# do.net
KiCad netlist of a schematic drawn in Altium Designer
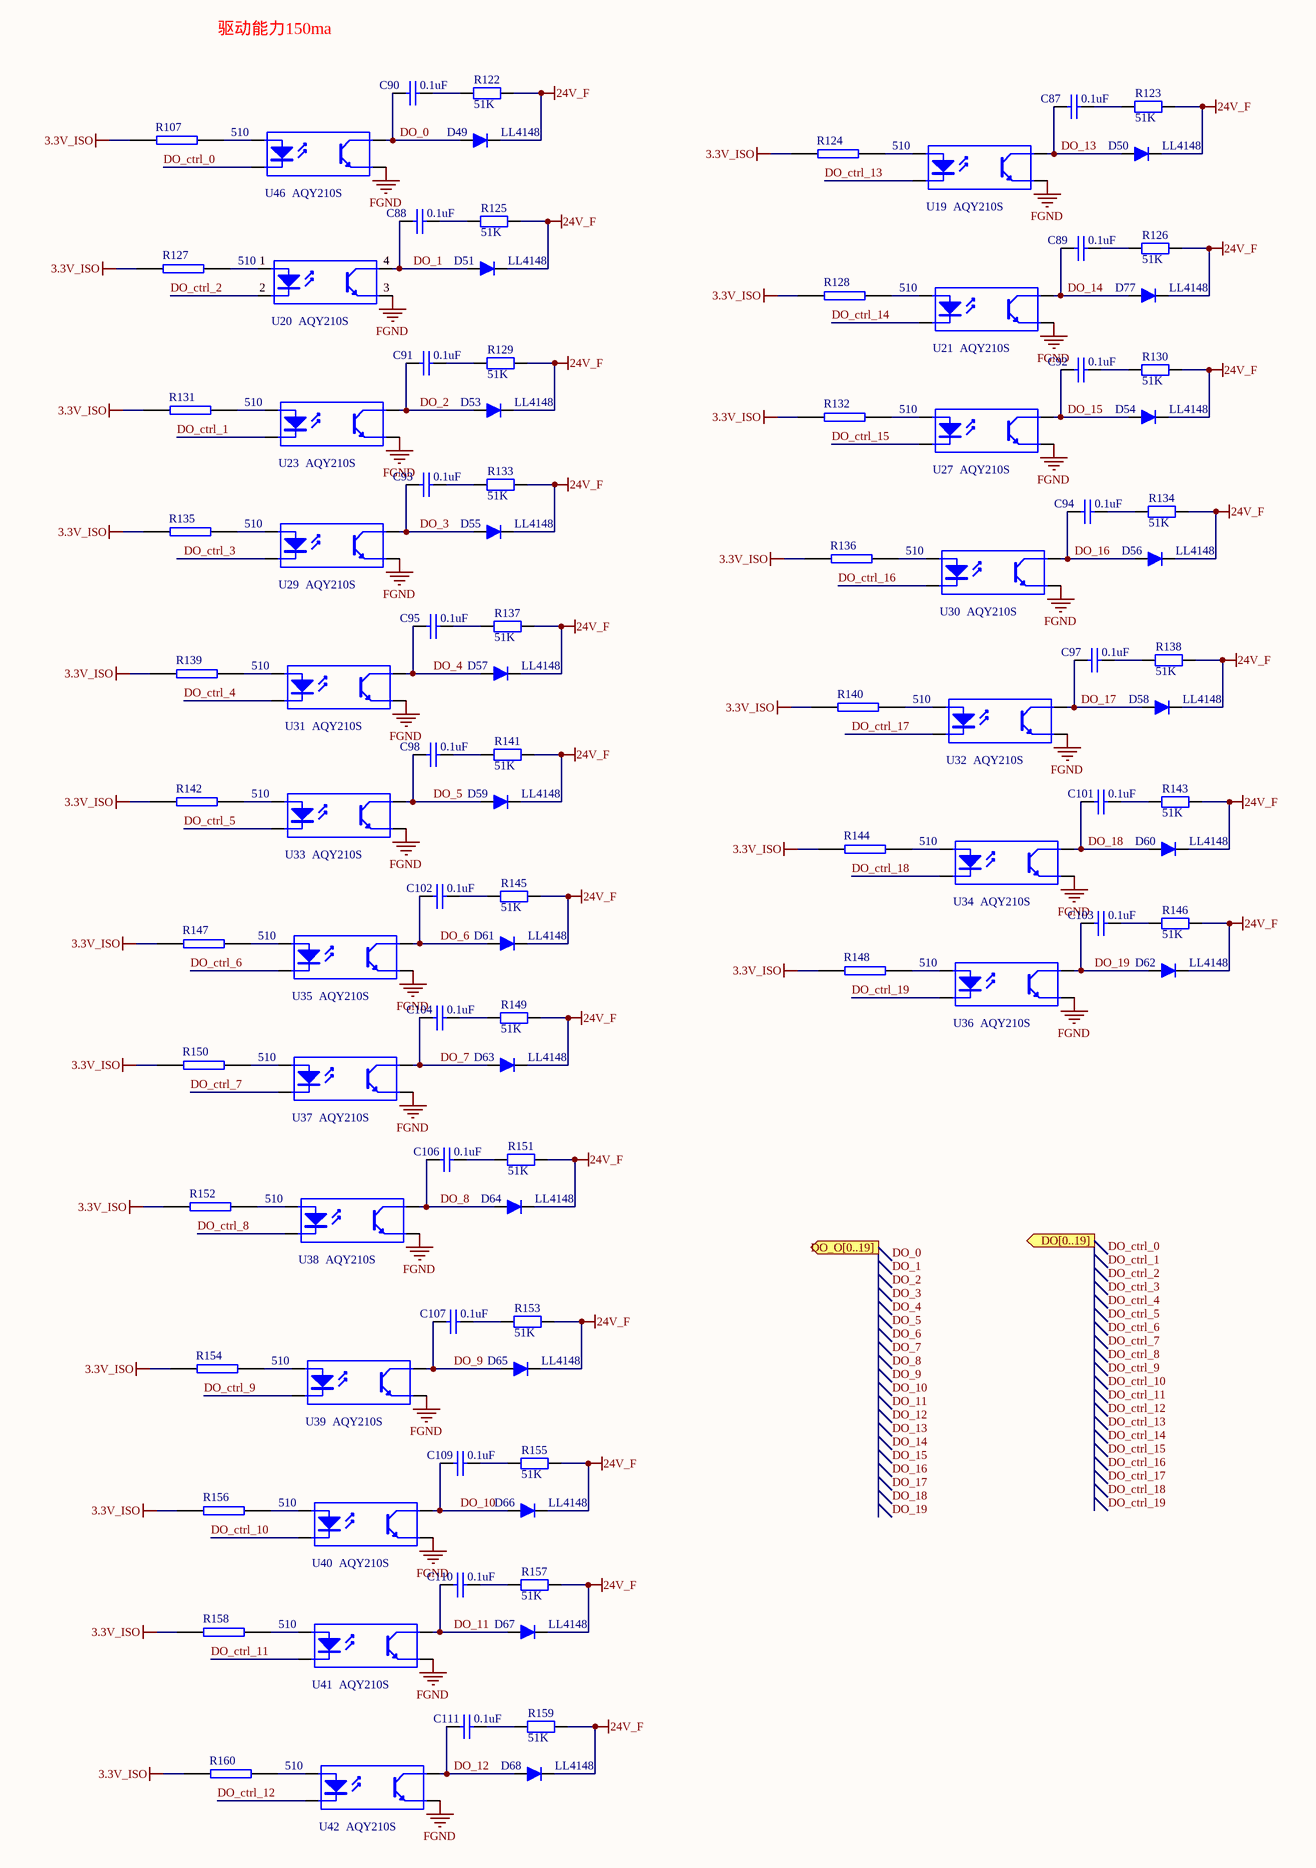
[diagram p0: do.SchDoc]

(export (version "E")
  (design (tool "Eeschema 10.0.6"))
  (components
    (comp (ref "C87")
      (value "0.1uF")
      (footprint "0603C")
      (description "Capacitor")
      (libsource (lib "*") (part "CAP"))
    )
    (comp (ref "C88")
      (value "0.1uF")
      (footprint "0603C")
      (description "Capacitor")
      (libsource (lib "*") (part "CAP"))
    )
    (comp (ref "C89")
      (value "0.1uF")
      (footprint "0603C")
      (description "Capacitor")
      (libsource (lib "*") (part "CAP"))
    )
    (comp (ref "C90")
      (value "0.1uF")
      (footprint "0603C")
      (description "Capacitor")
      (libsource (lib "*") (part "CAP"))
    )
    (comp (ref "C91")
      (value "0.1uF")
      (footprint "0603C")
      (description "Capacitor")
      (libsource (lib "*") (part "CAP"))
    )
    (comp (ref "C92")
      (value "0.1uF")
      (footprint "0603C")
      (description "Capacitor")
      (libsource (lib "*") (part "CAP"))
    )
    (comp (ref "C93")
      (value "0.1uF")
      (footprint "0603C")
      (description "Capacitor")
      (libsource (lib "*") (part "CAP"))
    )
    (comp (ref "C94")
      (value "0.1uF")
      (footprint "0603C")
      (description "Capacitor")
      (libsource (lib "*") (part "CAP"))
    )
    (comp (ref "C95")
      (value "0.1uF")
      (footprint "0603C")
      (description "Capacitor")
      (libsource (lib "*") (part "CAP"))
    )
    (comp (ref "C97")
      (value "0.1uF")
      (footprint "0603C")
      (description "Capacitor")
      (libsource (lib "*") (part "CAP"))
    )
    (comp (ref "C98")
      (value "0.1uF")
      (footprint "0603C")
      (description "Capacitor")
      (libsource (lib "*") (part "CAP"))
    )
    (comp (ref "C101")
      (value "0.1uF")
      (footprint "0603C")
      (description "Capacitor")
      (libsource (lib "*") (part "CAP"))
    )
    (comp (ref "C102")
      (value "0.1uF")
      (footprint "0603C")
      (description "Capacitor")
      (libsource (lib "*") (part "CAP"))
    )
    (comp (ref "C103")
      (value "0.1uF")
      (footprint "0603C")
      (description "Capacitor")
      (libsource (lib "*") (part "CAP"))
    )
    (comp (ref "C104")
      (value "0.1uF")
      (footprint "0603C")
      (description "Capacitor")
      (libsource (lib "*") (part "CAP"))
    )
    (comp (ref "C106")
      (value "0.1uF")
      (footprint "0603C")
      (description "Capacitor")
      (libsource (lib "*") (part "CAP"))
    )
    (comp (ref "C107")
      (value "0.1uF")
      (footprint "0603C")
      (description "Capacitor")
      (libsource (lib "*") (part "CAP"))
    )
    (comp (ref "C109")
      (value "0.1uF")
      (footprint "0603C")
      (description "Capacitor")
      (libsource (lib "*") (part "CAP"))
    )
    (comp (ref "C110")
      (value "0.1uF")
      (footprint "0603C")
      (description "Capacitor")
      (libsource (lib "*") (part "CAP"))
    )
    (comp (ref "C111")
      (value "0.1uF")
      (footprint "0603C")
      (description "Capacitor")
      (libsource (lib "*") (part "CAP"))
    )
    (comp (ref "D49")
      (value "LL4148")
      (footprint "DO-213AB/LL34/MiniMELF")
      (description "VISHAY,LL4148,圆柱体MiniMELF100V/2A,ROHS")
      (libsource (lib "Device2018") (part "LL4148"))
    )
    (comp (ref "D50")
      (value "LL4148")
      (footprint "DO-213AB/LL34/MiniMELF")
      (description "VISHAY,LL4148,圆柱体MiniMELF100V/2A,ROHS")
      (libsource (lib "Device2018") (part "LL4148"))
    )
    (comp (ref "D51")
      (value "LL4148")
      (footprint "DO-213AB/LL34/MiniMELF")
      (description "VISHAY,LL4148,圆柱体MiniMELF100V/2A,ROHS")
      (libsource (lib "Device2018") (part "LL4148"))
    )
    (comp (ref "D53")
      (value "LL4148")
      (footprint "DO-213AB/LL34/MiniMELF")
      (description "VISHAY,LL4148,圆柱体MiniMELF100V/2A,ROHS")
      (libsource (lib "Device2018") (part "LL4148"))
    )
    (comp (ref "D54")
      (value "LL4148")
      (footprint "DO-213AB/LL34/MiniMELF")
      (description "VISHAY,LL4148,圆柱体MiniMELF100V/2A,ROHS")
      (libsource (lib "Device2018") (part "LL4148"))
    )
    (comp (ref "D55")
      (value "LL4148")
      (footprint "DO-213AB/LL34/MiniMELF")
      (description "VISHAY,LL4148,圆柱体MiniMELF100V/2A,ROHS")
      (libsource (lib "Device2018") (part "LL4148"))
    )
    (comp (ref "D56")
      (value "LL4148")
      (footprint "DO-213AB/LL34/MiniMELF")
      (description "VISHAY,LL4148,圆柱体MiniMELF100V/2A,ROHS")
      (libsource (lib "Device2018") (part "LL4148"))
    )
    (comp (ref "D57")
      (value "LL4148")
      (footprint "DO-213AB/LL34/MiniMELF")
      (description "VISHAY,LL4148,圆柱体MiniMELF100V/2A,ROHS")
      (libsource (lib "Device2018") (part "LL4148"))
    )
    (comp (ref "D58")
      (value "LL4148")
      (footprint "DO-213AB/LL34/MiniMELF")
      (description "VISHAY,LL4148,圆柱体MiniMELF100V/2A,ROHS")
      (libsource (lib "Device2018") (part "LL4148"))
    )
    (comp (ref "D59")
      (value "LL4148")
      (footprint "DO-213AB/LL34/MiniMELF")
      (description "VISHAY,LL4148,圆柱体MiniMELF100V/2A,ROHS")
      (libsource (lib "Device2018") (part "LL4148"))
    )
    (comp (ref "D60")
      (value "LL4148")
      (footprint "DO-213AB/LL34/MiniMELF")
      (description "VISHAY,LL4148,圆柱体MiniMELF100V/2A,ROHS")
      (libsource (lib "Device2018") (part "LL4148"))
    )
    (comp (ref "D61")
      (value "LL4148")
      (footprint "DO-213AB/LL34/MiniMELF")
      (description "VISHAY,LL4148,圆柱体MiniMELF100V/2A,ROHS")
      (libsource (lib "Device2018") (part "LL4148"))
    )
    (comp (ref "D62")
      (value "LL4148")
      (footprint "DO-213AB/LL34/MiniMELF")
      (description "VISHAY,LL4148,圆柱体MiniMELF100V/2A,ROHS")
      (libsource (lib "Device2018") (part "LL4148"))
    )
    (comp (ref "D63")
      (value "LL4148")
      (footprint "DO-213AB/LL34/MiniMELF")
      (description "VISHAY,LL4148,圆柱体MiniMELF100V/2A,ROHS")
      (libsource (lib "Device2018") (part "LL4148"))
    )
    (comp (ref "D64")
      (value "LL4148")
      (footprint "DO-213AB/LL34/MiniMELF")
      (description "VISHAY,LL4148,圆柱体MiniMELF100V/2A,ROHS")
      (libsource (lib "Device2018") (part "LL4148"))
    )
    (comp (ref "D65")
      (value "LL4148")
      (footprint "DO-213AB/LL34/MiniMELF")
      (description "VISHAY,LL4148,圆柱体MiniMELF100V/2A,ROHS")
      (libsource (lib "Device2018") (part "LL4148"))
    )
    (comp (ref "D66")
      (value "LL4148")
      (footprint "DO-213AB/LL34/MiniMELF")
      (description "VISHAY,LL4148,圆柱体MiniMELF100V/2A,ROHS")
      (libsource (lib "Device2018") (part "LL4148"))
    )
    (comp (ref "D67")
      (value "LL4148")
      (footprint "DO-213AB/LL34/MiniMELF")
      (description "VISHAY,LL4148,圆柱体MiniMELF100V/2A,ROHS")
      (libsource (lib "Device2018") (part "LL4148"))
    )
    (comp (ref "D68")
      (value "LL4148")
      (footprint "DO-213AB/LL34/MiniMELF")
      (description "VISHAY,LL4148,圆柱体MiniMELF100V/2A,ROHS")
      (libsource (lib "Device2018") (part "LL4148"))
    )
    (comp (ref "D77")
      (value "LL4148")
      (footprint "DO-213AB/LL34/MiniMELF")
      (description "VISHAY,LL4148,圆柱体MiniMELF100V/2A,ROHS")
      (libsource (lib "Device2018") (part "LL4148"))
    )
    (comp (ref "R107") (value "510") (footprint "0603R") (libsource (lib "*") (part "RES2")))
    (comp (ref "R122") (value "51K") (footprint "0603R") (libsource (lib "MQlibrary") (part "Res0805M")))
    (comp (ref "R123") (value "51K") (footprint "0603R") (libsource (lib "MQlibrary") (part "Res0805M")))
    (comp (ref "R124") (value "510") (footprint "0603R") (libsource (lib "*") (part "RES2")))
    (comp (ref "R125") (value "51K") (footprint "0603R") (libsource (lib "MQlibrary") (part "Res0805M")))
    (comp (ref "R126") (value "51K") (footprint "0603R") (libsource (lib "MQlibrary") (part "Res0805M")))
    (comp (ref "R127") (value "510") (footprint "0603R") (libsource (lib "*") (part "RES2")))
    (comp (ref "R128") (value "510") (footprint "0603R") (libsource (lib "*") (part "RES2")))
    (comp (ref "R129") (value "51K") (footprint "0603R") (libsource (lib "MQlibrary") (part "Res0805M")))
    (comp (ref "R130") (value "51K") (footprint "0603R") (libsource (lib "MQlibrary") (part "Res0805M")))
    (comp (ref "R131") (value "510") (footprint "0603R") (libsource (lib "*") (part "RES2")))
    (comp (ref "R132") (value "510") (footprint "0603R") (libsource (lib "*") (part "RES2")))
    (comp (ref "R133") (value "51K") (footprint "0603R") (libsource (lib "MQlibrary") (part "Res0805M")))
    (comp (ref "R134") (value "51K") (footprint "0603R") (libsource (lib "MQlibrary") (part "Res0805M")))
    (comp (ref "R135") (value "510") (footprint "0603R") (libsource (lib "*") (part "RES2")))
    (comp (ref "R136") (value "510") (footprint "0603R") (libsource (lib "*") (part "RES2")))
    (comp (ref "R137") (value "51K") (footprint "0603R") (libsource (lib "MQlibrary") (part "Res0805M")))
    (comp (ref "R138") (value "51K") (footprint "0603R") (libsource (lib "MQlibrary") (part "Res0805M")))
    (comp (ref "R139") (value "510") (footprint "0603R") (libsource (lib "*") (part "RES2")))
    (comp (ref "R140") (value "510") (footprint "0603R") (libsource (lib "*") (part "RES2")))
    (comp (ref "R141") (value "51K") (footprint "0603R") (libsource (lib "MQlibrary") (part "Res0805M")))
    (comp (ref "R142") (value "510") (footprint "0603R") (libsource (lib "*") (part "RES2")))
    (comp (ref "R143") (value "51K") (footprint "0603R") (libsource (lib "MQlibrary") (part "Res0805M")))
    (comp (ref "R144") (value "510") (footprint "0603R") (libsource (lib "*") (part "RES2")))
    (comp (ref "R145") (value "51K") (footprint "0603R") (libsource (lib "MQlibrary") (part "Res0805M")))
    (comp (ref "R146") (value "51K") (footprint "0603R") (libsource (lib "MQlibrary") (part "Res0805M")))
    (comp (ref "R147") (value "510") (footprint "0603R") (libsource (lib "*") (part "RES2")))
    (comp (ref "R148") (value "510") (footprint "0603R") (libsource (lib "*") (part "RES2")))
    (comp (ref "R149") (value "51K") (footprint "0603R") (libsource (lib "MQlibrary") (part "Res0805M")))
    (comp (ref "R150") (value "510") (footprint "0603R") (libsource (lib "*") (part "RES2")))
    (comp (ref "R151") (value "51K") (footprint "0603R") (libsource (lib "MQlibrary") (part "Res0805M")))
    (comp (ref "R152") (value "510") (footprint "0603R") (libsource (lib "*") (part "RES2")))
    (comp (ref "R153") (value "51K") (footprint "0603R") (libsource (lib "MQlibrary") (part "Res0805M")))
    (comp (ref "R154") (value "510") (footprint "0603R") (libsource (lib "*") (part "RES2")))
    (comp (ref "R155") (value "51K") (footprint "0603R") (libsource (lib "MQlibrary") (part "Res0805M")))
    (comp (ref "R156") (value "510") (footprint "0603R") (libsource (lib "*") (part "RES2")))
    (comp (ref "R157") (value "51K") (footprint "0603R") (libsource (lib "MQlibrary") (part "Res0805M")))
    (comp (ref "R158") (value "510") (footprint "0603R") (libsource (lib "*") (part "RES2")))
    (comp (ref "R159") (value "51K") (footprint "0603R") (libsource (lib "MQlibrary") (part "Res0805M")))
    (comp (ref "R160") (value "510") (footprint "0603R") (libsource (lib "*") (part "RES2")))
    (comp (ref "U19")
      (value "AQY210S")
      (footprint "sop4")
      (description "4-Pin Phototransistor Optocoupler")
      (fields (field (name "PUBLISHER") "Altium Limited"))
      (libsource (lib "Miscellaneous Devices") (part "Optoisolator1"))
    )
    (comp (ref "U20")
      (value "AQY210S")
      (footprint "sop4")
      (description "4-Pin Phototransistor Optocoupler")
      (fields (field (name "PUBLISHER") "Altium Limited"))
      (libsource (lib "") (part "Optoisolator1_1"))
    )
    (comp (ref "U21")
      (value "AQY210S")
      (footprint "sop4")
      (description "4-Pin Phototransistor Optocoupler")
      (fields (field (name "PUBLISHER") "Altium Limited"))
      (libsource (lib "Miscellaneous Devices") (part "Optoisolator1"))
    )
    (comp (ref "U23")
      (value "AQY210S")
      (footprint "sop4")
      (description "4-Pin Phototransistor Optocoupler")
      (fields (field (name "PUBLISHER") "Altium Limited"))
      (libsource (lib "Miscellaneous Devices") (part "Optoisolator1"))
    )
    (comp (ref "U27")
      (value "AQY210S")
      (footprint "sop4")
      (description "4-Pin Phototransistor Optocoupler")
      (fields (field (name "PUBLISHER") "Altium Limited"))
      (libsource (lib "Miscellaneous Devices") (part "Optoisolator1"))
    )
    (comp (ref "U29")
      (value "AQY210S")
      (footprint "sop4")
      (description "4-Pin Phototransistor Optocoupler")
      (fields (field (name "PUBLISHER") "Altium Limited"))
      (libsource (lib "Miscellaneous Devices") (part "Optoisolator1"))
    )
    (comp (ref "U30")
      (value "AQY210S")
      (footprint "sop4")
      (description "4-Pin Phototransistor Optocoupler")
      (fields (field (name "PUBLISHER") "Altium Limited"))
      (libsource (lib "Miscellaneous Devices") (part "Optoisolator1"))
    )
    (comp (ref "U31")
      (value "AQY210S")
      (footprint "sop4")
      (description "4-Pin Phototransistor Optocoupler")
      (fields (field (name "PUBLISHER") "Altium Limited"))
      (libsource (lib "Miscellaneous Devices") (part "Optoisolator1"))
    )
    (comp (ref "U32")
      (value "AQY210S")
      (footprint "sop4")
      (description "4-Pin Phototransistor Optocoupler")
      (fields (field (name "PUBLISHER") "Altium Limited"))
      (libsource (lib "Miscellaneous Devices") (part "Optoisolator1"))
    )
    (comp (ref "U33")
      (value "AQY210S")
      (footprint "sop4")
      (description "4-Pin Phototransistor Optocoupler")
      (fields (field (name "PUBLISHER") "Altium Limited"))
      (libsource (lib "Miscellaneous Devices") (part "Optoisolator1"))
    )
    (comp (ref "U34")
      (value "AQY210S")
      (footprint "sop4")
      (description "4-Pin Phototransistor Optocoupler")
      (fields (field (name "PUBLISHER") "Altium Limited"))
      (libsource (lib "Miscellaneous Devices") (part "Optoisolator1"))
    )
    (comp (ref "U35")
      (value "AQY210S")
      (footprint "sop4")
      (description "4-Pin Phototransistor Optocoupler")
      (fields (field (name "PUBLISHER") "Altium Limited"))
      (libsource (lib "Miscellaneous Devices") (part "Optoisolator1"))
    )
    (comp (ref "U36")
      (value "AQY210S")
      (footprint "sop4")
      (description "4-Pin Phototransistor Optocoupler")
      (fields (field (name "PUBLISHER") "Altium Limited"))
      (libsource (lib "Miscellaneous Devices") (part "Optoisolator1"))
    )
    (comp (ref "U37")
      (value "AQY210S")
      (footprint "sop4")
      (description "4-Pin Phototransistor Optocoupler")
      (fields (field (name "PUBLISHER") "Altium Limited"))
      (libsource (lib "Miscellaneous Devices") (part "Optoisolator1"))
    )
    (comp (ref "U38")
      (value "AQY210S")
      (footprint "sop4")
      (description "4-Pin Phototransistor Optocoupler")
      (fields (field (name "PUBLISHER") "Altium Limited"))
      (libsource (lib "Miscellaneous Devices") (part "Optoisolator1"))
    )
    (comp (ref "U39")
      (value "AQY210S")
      (footprint "sop4")
      (description "4-Pin Phototransistor Optocoupler")
      (fields (field (name "PUBLISHER") "Altium Limited"))
      (libsource (lib "Miscellaneous Devices") (part "Optoisolator1"))
    )
    (comp (ref "U40")
      (value "AQY210S")
      (footprint "sop4")
      (description "4-Pin Phototransistor Optocoupler")
      (fields (field (name "PUBLISHER") "Altium Limited"))
      (libsource (lib "Miscellaneous Devices") (part "Optoisolator1"))
    )
    (comp (ref "U41")
      (value "AQY210S")
      (footprint "sop4")
      (description "4-Pin Phototransistor Optocoupler")
      (fields (field (name "PUBLISHER") "Altium Limited"))
      (libsource (lib "Miscellaneous Devices") (part "Optoisolator1"))
    )
    (comp (ref "U42")
      (value "AQY210S")
      (footprint "sop4")
      (description "4-Pin Phototransistor Optocoupler")
      (fields (field (name "PUBLISHER") "Altium Limited"))
      (libsource (lib "Miscellaneous Devices") (part "Optoisolator1"))
    )
    (comp (ref "U46")
      (value "AQY210S")
      (footprint "sop4")
      (description "4-Pin Phototransistor Optocoupler")
      (fields (field (name "PUBLISHER") "Altium Limited"))
      (libsource (lib "Miscellaneous Devices") (part "Optoisolator1"))
    )
  )
  (nets
    (net (code "42") (name "/DO_0") (class "Default")
      (node (ref "C90") (pin "1") (pinfunction "1_1") (pintype "passive"))
      (node (ref "D49") (pin "2") (pinfunction "2_2") (pintype "passive"))
      (node (ref "U46") (pin "4") (pinfunction "C_4") (pintype "passive"))
    )
    (net (code "43") (name "/DO_1") (class "Default")
      (node (ref "C88") (pin "1") (pinfunction "1_1") (pintype "passive"))
      (node (ref "D51") (pin "2") (pinfunction "2_2") (pintype "passive"))
      (node (ref "U20") (pin "4") (pinfunction "C_4") (pintype "passive"))
    )
    (net (code "44") (name "/DO_2") (class "Default")
      (node (ref "C91") (pin "1") (pinfunction "1_1") (pintype "passive"))
      (node (ref "D53") (pin "2") (pinfunction "2_2") (pintype "passive"))
      (node (ref "U23") (pin "4") (pinfunction "C_4") (pintype "passive"))
    )
    (net (code "45") (name "/DO_3") (class "Default")
      (node (ref "C93") (pin "1") (pinfunction "1_1") (pintype "passive"))
      (node (ref "D55") (pin "2") (pinfunction "2_2") (pintype "passive"))
      (node (ref "U29") (pin "4") (pinfunction "C_4") (pintype "passive"))
    )
    (net (code "46") (name "/DO_4") (class "Default")
      (node (ref "C95") (pin "1") (pinfunction "1_1") (pintype "passive"))
      (node (ref "D57") (pin "2") (pinfunction "2_2") (pintype "passive"))
      (node (ref "U31") (pin "4") (pinfunction "C_4") (pintype "passive"))
    )
    (net (code "47") (name "/DO_5") (class "Default")
      (node (ref "C98") (pin "1") (pinfunction "1_1") (pintype "passive"))
      (node (ref "D59") (pin "2") (pinfunction "2_2") (pintype "passive"))
      (node (ref "U33") (pin "4") (pinfunction "C_4") (pintype "passive"))
    )
    (net (code "48") (name "/DO_6") (class "Default")
      (node (ref "C102") (pin "1") (pinfunction "1_1") (pintype "passive"))
      (node (ref "D61") (pin "2") (pinfunction "2_2") (pintype "passive"))
      (node (ref "U35") (pin "4") (pinfunction "C_4") (pintype "passive"))
    )
    (net (code "49") (name "/DO_7") (class "Default")
      (node (ref "C104") (pin "1") (pinfunction "1_1") (pintype "passive"))
      (node (ref "D63") (pin "2") (pinfunction "2_2") (pintype "passive"))
      (node (ref "U37") (pin "4") (pinfunction "C_4") (pintype "passive"))
    )
    (net (code "50") (name "/DO_8") (class "Default")
      (node (ref "C106") (pin "1") (pinfunction "1_1") (pintype "passive"))
      (node (ref "D64") (pin "2") (pinfunction "2_2") (pintype "passive"))
      (node (ref "U38") (pin "4") (pinfunction "C_4") (pintype "passive"))
    )
    (net (code "51") (name "/DO_9") (class "Default")
      (node (ref "C107") (pin "1") (pinfunction "1_1") (pintype "passive"))
      (node (ref "D65") (pin "2") (pinfunction "2_2") (pintype "passive"))
      (node (ref "U39") (pin "4") (pinfunction "C_4") (pintype "passive"))
    )
    (net (code "52") (name "/DO_10") (class "Default")
      (node (ref "C109") (pin "1") (pinfunction "1_1") (pintype "passive"))
      (node (ref "D66") (pin "2") (pinfunction "2_2") (pintype "passive"))
      (node (ref "U40") (pin "4") (pinfunction "C_4") (pintype "passive"))
    )
    (net (code "53") (name "/DO_11") (class "Default")
      (node (ref "C110") (pin "1") (pinfunction "1_1") (pintype "passive"))
      (node (ref "D67") (pin "2") (pinfunction "2_2") (pintype "passive"))
      (node (ref "U41") (pin "4") (pinfunction "C_4") (pintype "passive"))
    )
    (net (code "54") (name "/DO_12") (class "Default")
      (node (ref "C111") (pin "1") (pinfunction "1_1") (pintype "passive"))
      (node (ref "D68") (pin "2") (pinfunction "2_2") (pintype "passive"))
      (node (ref "U42") (pin "4") (pinfunction "C_4") (pintype "passive"))
    )
    (net (code "55") (name "/DO_13") (class "Default")
      (node (ref "C87") (pin "1") (pinfunction "1_1") (pintype "passive"))
      (node (ref "D50") (pin "2") (pinfunction "2_2") (pintype "passive"))
      (node (ref "U19") (pin "4") (pinfunction "C_4") (pintype "passive"))
    )
    (net (code "56") (name "/DO_14") (class "Default")
      (node (ref "C89") (pin "1") (pinfunction "1_1") (pintype "passive"))
      (node (ref "D77") (pin "2") (pinfunction "2_2") (pintype "passive"))
      (node (ref "U21") (pin "4") (pinfunction "C_4") (pintype "passive"))
    )
    (net (code "57") (name "/DO_15") (class "Default")
      (node (ref "C92") (pin "1") (pinfunction "1_1") (pintype "passive"))
      (node (ref "D54") (pin "2") (pinfunction "2_2") (pintype "passive"))
      (node (ref "U27") (pin "4") (pinfunction "C_4") (pintype "passive"))
    )
    (net (code "58") (name "/DO_16") (class "Default")
      (node (ref "C94") (pin "1") (pinfunction "1_1") (pintype "passive"))
      (node (ref "D56") (pin "2") (pinfunction "2_2") (pintype "passive"))
      (node (ref "U30") (pin "4") (pinfunction "C_4") (pintype "passive"))
    )
    (net (code "59") (name "/DO_17") (class "Default")
      (node (ref "C97") (pin "1") (pinfunction "1_1") (pintype "passive"))
      (node (ref "D58") (pin "2") (pinfunction "2_2") (pintype "passive"))
      (node (ref "U32") (pin "4") (pinfunction "C_4") (pintype "passive"))
    )
    (net (code "60") (name "/DO_18") (class "Default")
      (node (ref "C101") (pin "1") (pinfunction "1_1") (pintype "passive"))
      (node (ref "D60") (pin "2") (pinfunction "2_2") (pintype "passive"))
      (node (ref "U34") (pin "4") (pinfunction "C_4") (pintype "passive"))
    )
    (net (code "61") (name "/DO_19") (class "Default")
      (node (ref "C103") (pin "1") (pinfunction "1_1") (pintype "passive"))
      (node (ref "D62") (pin "2") (pinfunction "2_2") (pintype "passive"))
      (node (ref "U36") (pin "4") (pinfunction "C_4") (pintype "passive"))
    )
    (net (code "63") (name "/DO_ctrl_0") (class "Default")
      (node (ref "U46") (pin "2") (pinfunction "K_2") (pintype "passive"))
    )
    (net (code "64") (name "/DO_ctrl_1") (class "Default")
      (node (ref "U23") (pin "2") (pinfunction "K_2") (pintype "passive"))
    )
    (net (code "65") (name "/DO_ctrl_2") (class "Default")
      (node (ref "U20") (pin "2") (pinfunction "K_2") (pintype "passive"))
    )
    (net (code "66") (name "/DO_ctrl_3") (class "Default")
      (node (ref "U29") (pin "2") (pinfunction "K_2") (pintype "passive"))
    )
    (net (code "67") (name "/DO_ctrl_4") (class "Default")
      (node (ref "U31") (pin "2") (pinfunction "K_2") (pintype "passive"))
    )
    (net (code "68") (name "/DO_ctrl_5") (class "Default")
      (node (ref "U33") (pin "2") (pinfunction "K_2") (pintype "passive"))
    )
    (net (code "69") (name "/DO_ctrl_6") (class "Default")
      (node (ref "U35") (pin "2") (pinfunction "K_2") (pintype "passive"))
    )
    (net (code "70") (name "/DO_ctrl_7") (class "Default")
      (node (ref "U37") (pin "2") (pinfunction "K_2") (pintype "passive"))
    )
    (net (code "71") (name "/DO_ctrl_8") (class "Default")
      (node (ref "U38") (pin "2") (pinfunction "K_2") (pintype "passive"))
    )
    (net (code "72") (name "/DO_ctrl_9") (class "Default")
      (node (ref "U39") (pin "2") (pinfunction "K_2") (pintype "passive"))
    )
    (net (code "73") (name "/DO_ctrl_10") (class "Default")
      (node (ref "U40") (pin "2") (pinfunction "K_2") (pintype "passive"))
    )
    (net (code "74") (name "/DO_ctrl_11") (class "Default")
      (node (ref "U41") (pin "2") (pinfunction "K_2") (pintype "passive"))
    )
    (net (code "75") (name "/DO_ctrl_12") (class "Default")
      (node (ref "U42") (pin "2") (pinfunction "K_2") (pintype "passive"))
    )
    (net (code "76") (name "/DO_ctrl_13") (class "Default")
      (node (ref "U19") (pin "2") (pinfunction "K_2") (pintype "passive"))
    )
    (net (code "77") (name "/DO_ctrl_14") (class "Default")
      (node (ref "U21") (pin "2") (pinfunction "K_2") (pintype "passive"))
    )
    (net (code "78") (name "/DO_ctrl_15") (class "Default")
      (node (ref "U27") (pin "2") (pinfunction "K_2") (pintype "passive"))
    )
    (net (code "79") (name "/DO_ctrl_16") (class "Default")
      (node (ref "U30") (pin "2") (pinfunction "K_2") (pintype "passive"))
    )
    (net (code "80") (name "/DO_ctrl_17") (class "Default")
      (node (ref "U32") (pin "2") (pinfunction "K_2") (pintype "passive"))
    )
    (net (code "81") (name "/DO_ctrl_18") (class "Default")
      (node (ref "U34") (pin "2") (pinfunction "K_2") (pintype "passive"))
    )
    (net (code "82") (name "/DO_ctrl_19") (class "Default")
      (node (ref "U36") (pin "2") (pinfunction "K_2") (pintype "passive"))
    )
    (net (code "83") (name "3.3V_ISO") (class "Default")
      (node (ref "R107") (pin "2") (pinfunction "2_2") (pintype "passive"))
      (node (ref "R124") (pin "2") (pinfunction "2_2") (pintype "passive"))
      (node (ref "R127") (pin "2") (pinfunction "2_2") (pintype "passive"))
      (node (ref "R128") (pin "2") (pinfunction "2_2") (pintype "passive"))
      (node (ref "R131") (pin "2") (pinfunction "2_2") (pintype "passive"))
      (node (ref "R132") (pin "2") (pinfunction "2_2") (pintype "passive"))
      (node (ref "R135") (pin "2") (pinfunction "2_2") (pintype "passive"))
      (node (ref "R136") (pin "2") (pinfunction "2_2") (pintype "passive"))
      (node (ref "R139") (pin "2") (pinfunction "2_2") (pintype "passive"))
      (node (ref "R140") (pin "2") (pinfunction "2_2") (pintype "passive"))
      (node (ref "R142") (pin "2") (pinfunction "2_2") (pintype "passive"))
      (node (ref "R144") (pin "2") (pinfunction "2_2") (pintype "passive"))
      (node (ref "R147") (pin "2") (pinfunction "2_2") (pintype "passive"))
      (node (ref "R148") (pin "2") (pinfunction "2_2") (pintype "passive"))
      (node (ref "R150") (pin "2") (pinfunction "2_2") (pintype "passive"))
      (node (ref "R152") (pin "2") (pinfunction "2_2") (pintype "passive"))
      (node (ref "R154") (pin "2") (pinfunction "2_2") (pintype "passive"))
      (node (ref "R156") (pin "2") (pinfunction "2_2") (pintype "passive"))
      (node (ref "R158") (pin "2") (pinfunction "2_2") (pintype "passive"))
      (node (ref "R160") (pin "2") (pinfunction "2_2") (pintype "passive"))
    )
    (net (code "84") (name "24V_F") (class "Default")
      (node (ref "D49") (pin "1") (pinfunction "1_1") (pintype "passive"))
      (node (ref "D50") (pin "1") (pinfunction "1_1") (pintype "passive"))
      (node (ref "D51") (pin "1") (pinfunction "1_1") (pintype "passive"))
      (node (ref "D53") (pin "1") (pinfunction "1_1") (pintype "passive"))
      (node (ref "D54") (pin "1") (pinfunction "1_1") (pintype "passive"))
      (node (ref "D55") (pin "1") (pinfunction "1_1") (pintype "passive"))
      (node (ref "D56") (pin "1") (pinfunction "1_1") (pintype "passive"))
      (node (ref "D57") (pin "1") (pinfunction "1_1") (pintype "passive"))
      (node (ref "D58") (pin "1") (pinfunction "1_1") (pintype "passive"))
      (node (ref "D59") (pin "1") (pinfunction "1_1") (pintype "passive"))
      (node (ref "D60") (pin "1") (pinfunction "1_1") (pintype "passive"))
      (node (ref "D61") (pin "1") (pinfunction "1_1") (pintype "passive"))
      (node (ref "D62") (pin "1") (pinfunction "1_1") (pintype "passive"))
      (node (ref "D63") (pin "1") (pinfunction "1_1") (pintype "passive"))
      (node (ref "D64") (pin "1") (pinfunction "1_1") (pintype "passive"))
      (node (ref "D65") (pin "1") (pinfunction "1_1") (pintype "passive"))
      (node (ref "D66") (pin "1") (pinfunction "1_1") (pintype "passive"))
      (node (ref "D67") (pin "1") (pinfunction "1_1") (pintype "passive"))
      (node (ref "D68") (pin "1") (pinfunction "1_1") (pintype "passive"))
      (node (ref "D77") (pin "1") (pinfunction "1_1") (pintype "passive"))
      (node (ref "R122") (pin "2") (pinfunction "2_2") (pintype "passive"))
      (node (ref "R123") (pin "2") (pinfunction "2_2") (pintype "passive"))
      (node (ref "R125") (pin "2") (pinfunction "2_2") (pintype "passive"))
      (node (ref "R126") (pin "2") (pinfunction "2_2") (pintype "passive"))
      (node (ref "R129") (pin "2") (pinfunction "2_2") (pintype "passive"))
      (node (ref "R130") (pin "2") (pinfunction "2_2") (pintype "passive"))
      (node (ref "R133") (pin "2") (pinfunction "2_2") (pintype "passive"))
      (node (ref "R134") (pin "2") (pinfunction "2_2") (pintype "passive"))
      (node (ref "R137") (pin "2") (pinfunction "2_2") (pintype "passive"))
      (node (ref "R138") (pin "2") (pinfunction "2_2") (pintype "passive"))
      (node (ref "R141") (pin "2") (pinfunction "2_2") (pintype "passive"))
      (node (ref "R143") (pin "2") (pinfunction "2_2") (pintype "passive"))
      (node (ref "R145") (pin "2") (pinfunction "2_2") (pintype "passive"))
      (node (ref "R146") (pin "2") (pinfunction "2_2") (pintype "passive"))
      (node (ref "R149") (pin "2") (pinfunction "2_2") (pintype "passive"))
      (node (ref "R151") (pin "2") (pinfunction "2_2") (pintype "passive"))
      (node (ref "R153") (pin "2") (pinfunction "2_2") (pintype "passive"))
      (node (ref "R155") (pin "2") (pinfunction "2_2") (pintype "passive"))
      (node (ref "R157") (pin "2") (pinfunction "2_2") (pintype "passive"))
      (node (ref "R159") (pin "2") (pinfunction "2_2") (pintype "passive"))
    )
    (net (code "85") (name "FGND") (class "Default")
      (node (ref "U19") (pin "3") (pinfunction "E_3") (pintype "passive"))
      (node (ref "U20") (pin "3") (pinfunction "E_3") (pintype "passive"))
      (node (ref "U21") (pin "3") (pinfunction "E_3") (pintype "passive"))
      (node (ref "U23") (pin "3") (pinfunction "E_3") (pintype "passive"))
      (node (ref "U27") (pin "3") (pinfunction "E_3") (pintype "passive"))
      (node (ref "U29") (pin "3") (pinfunction "E_3") (pintype "passive"))
      (node (ref "U30") (pin "3") (pinfunction "E_3") (pintype "passive"))
      (node (ref "U31") (pin "3") (pinfunction "E_3") (pintype "passive"))
      (node (ref "U32") (pin "3") (pinfunction "E_3") (pintype "passive"))
      (node (ref "U33") (pin "3") (pinfunction "E_3") (pintype "passive"))
      (node (ref "U34") (pin "3") (pinfunction "E_3") (pintype "passive"))
      (node (ref "U35") (pin "3") (pinfunction "E_3") (pintype "passive"))
      (node (ref "U36") (pin "3") (pinfunction "E_3") (pintype "passive"))
      (node (ref "U37") (pin "3") (pinfunction "E_3") (pintype "passive"))
      (node (ref "U38") (pin "3") (pinfunction "E_3") (pintype "passive"))
      (node (ref "U39") (pin "3") (pinfunction "E_3") (pintype "passive"))
      (node (ref "U40") (pin "3") (pinfunction "E_3") (pintype "passive"))
      (node (ref "U41") (pin "3") (pinfunction "E_3") (pintype "passive"))
      (node (ref "U42") (pin "3") (pinfunction "E_3") (pintype "passive"))
      (node (ref "U46") (pin "3") (pinfunction "E_3") (pintype "passive"))
    )
    (net (code "86") (name "Net-(C87-Pad2)") (class "Default")
      (node (ref "C87") (pin "2") (pinfunction "2_2") (pintype "passive"))
      (node (ref "R123") (pin "1") (pinfunction "1_1") (pintype "passive"))
    )
    (net (code "87") (name "Net-(C88-Pad2)") (class "Default")
      (node (ref "C88") (pin "2") (pinfunction "2_2") (pintype "passive"))
      (node (ref "R125") (pin "1") (pinfunction "1_1") (pintype "passive"))
    )
    (net (code "88") (name "Net-(C89-Pad2)") (class "Default")
      (node (ref "C89") (pin "2") (pinfunction "2_2") (pintype "passive"))
      (node (ref "R126") (pin "1") (pinfunction "1_1") (pintype "passive"))
    )
    (net (code "89") (name "Net-(C90-Pad2)") (class "Default")
      (node (ref "C90") (pin "2") (pinfunction "2_2") (pintype "passive"))
      (node (ref "R122") (pin "1") (pinfunction "1_1") (pintype "passive"))
    )
    (net (code "90") (name "Net-(C91-Pad2)") (class "Default")
      (node (ref "C91") (pin "2") (pinfunction "2_2") (pintype "passive"))
      (node (ref "R129") (pin "1") (pinfunction "1_1") (pintype "passive"))
    )
    (net (code "91") (name "Net-(C92-Pad2)") (class "Default")
      (node (ref "C92") (pin "2") (pinfunction "2_2") (pintype "passive"))
      (node (ref "R130") (pin "1") (pinfunction "1_1") (pintype "passive"))
    )
    (net (code "92") (name "Net-(C93-Pad2)") (class "Default")
      (node (ref "C93") (pin "2") (pinfunction "2_2") (pintype "passive"))
      (node (ref "R133") (pin "1") (pinfunction "1_1") (pintype "passive"))
    )
    (net (code "93") (name "Net-(C94-Pad2)") (class "Default")
      (node (ref "C94") (pin "2") (pinfunction "2_2") (pintype "passive"))
      (node (ref "R134") (pin "1") (pinfunction "1_1") (pintype "passive"))
    )
    (net (code "94") (name "Net-(C95-Pad2)") (class "Default")
      (node (ref "C95") (pin "2") (pinfunction "2_2") (pintype "passive"))
      (node (ref "R137") (pin "1") (pinfunction "1_1") (pintype "passive"))
    )
    (net (code "95") (name "Net-(C97-Pad2)") (class "Default")
      (node (ref "C97") (pin "2") (pinfunction "2_2") (pintype "passive"))
      (node (ref "R138") (pin "1") (pinfunction "1_1") (pintype "passive"))
    )
    (net (code "96") (name "Net-(C98-Pad2)") (class "Default")
      (node (ref "C98") (pin "2") (pinfunction "2_2") (pintype "passive"))
      (node (ref "R141") (pin "1") (pinfunction "1_1") (pintype "passive"))
    )
    (net (code "97") (name "Net-(C101-Pad2)") (class "Default")
      (node (ref "C101") (pin "2") (pinfunction "2_2") (pintype "passive"))
      (node (ref "R143") (pin "1") (pinfunction "1_1") (pintype "passive"))
    )
    (net (code "98") (name "Net-(C102-Pad2)") (class "Default")
      (node (ref "C102") (pin "2") (pinfunction "2_2") (pintype "passive"))
      (node (ref "R145") (pin "1") (pinfunction "1_1") (pintype "passive"))
    )
    (net (code "99") (name "Net-(C103-Pad2)") (class "Default")
      (node (ref "C103") (pin "2") (pinfunction "2_2") (pintype "passive"))
      (node (ref "R146") (pin "1") (pinfunction "1_1") (pintype "passive"))
    )
    (net (code "100") (name "Net-(C104-Pad2)") (class "Default")
      (node (ref "C104") (pin "2") (pinfunction "2_2") (pintype "passive"))
      (node (ref "R149") (pin "1") (pinfunction "1_1") (pintype "passive"))
    )
    (net (code "101") (name "Net-(C106-Pad2)") (class "Default")
      (node (ref "C106") (pin "2") (pinfunction "2_2") (pintype "passive"))
      (node (ref "R151") (pin "1") (pinfunction "1_1") (pintype "passive"))
    )
    (net (code "102") (name "Net-(C107-Pad2)") (class "Default")
      (node (ref "C107") (pin "2") (pinfunction "2_2") (pintype "passive"))
      (node (ref "R153") (pin "1") (pinfunction "1_1") (pintype "passive"))
    )
    (net (code "103") (name "Net-(C109-Pad2)") (class "Default")
      (node (ref "C109") (pin "2") (pinfunction "2_2") (pintype "passive"))
      (node (ref "R155") (pin "1") (pinfunction "1_1") (pintype "passive"))
    )
    (net (code "104") (name "Net-(C110-Pad2)") (class "Default")
      (node (ref "C110") (pin "2") (pinfunction "2_2") (pintype "passive"))
      (node (ref "R157") (pin "1") (pinfunction "1_1") (pintype "passive"))
    )
    (net (code "105") (name "Net-(C111-Pad2)") (class "Default")
      (node (ref "C111") (pin "2") (pinfunction "2_2") (pintype "passive"))
      (node (ref "R159") (pin "1") (pinfunction "1_1") (pintype "passive"))
    )
    (net (code "106") (name "Net-(U19-A)") (class "Default")
      (node (ref "R124") (pin "1") (pinfunction "1_1") (pintype "passive"))
      (node (ref "U19") (pin "1") (pinfunction "A_1") (pintype "passive"))
    )
    (net (code "107") (name "Net-(U20-A)") (class "Default")
      (node (ref "R127") (pin "1") (pinfunction "1_1") (pintype "passive"))
      (node (ref "U20") (pin "1") (pinfunction "A_1") (pintype "passive"))
    )
    (net (code "108") (name "Net-(U21-A)") (class "Default")
      (node (ref "R128") (pin "1") (pinfunction "1_1") (pintype "passive"))
      (node (ref "U21") (pin "1") (pinfunction "A_1") (pintype "passive"))
    )
    (net (code "109") (name "Net-(U23-A)") (class "Default")
      (node (ref "R131") (pin "1") (pinfunction "1_1") (pintype "passive"))
      (node (ref "U23") (pin "1") (pinfunction "A_1") (pintype "passive"))
    )
    (net (code "110") (name "Net-(U27-A)") (class "Default")
      (node (ref "R132") (pin "1") (pinfunction "1_1") (pintype "passive"))
      (node (ref "U27") (pin "1") (pinfunction "A_1") (pintype "passive"))
    )
    (net (code "111") (name "Net-(U29-A)") (class "Default")
      (node (ref "R135") (pin "1") (pinfunction "1_1") (pintype "passive"))
      (node (ref "U29") (pin "1") (pinfunction "A_1") (pintype "passive"))
    )
    (net (code "112") (name "Net-(U30-A)") (class "Default")
      (node (ref "R136") (pin "1") (pinfunction "1_1") (pintype "passive"))
      (node (ref "U30") (pin "1") (pinfunction "A_1") (pintype "passive"))
    )
    (net (code "113") (name "Net-(U31-A)") (class "Default")
      (node (ref "R139") (pin "1") (pinfunction "1_1") (pintype "passive"))
      (node (ref "U31") (pin "1") (pinfunction "A_1") (pintype "passive"))
    )
    (net (code "114") (name "Net-(U32-A)") (class "Default")
      (node (ref "R140") (pin "1") (pinfunction "1_1") (pintype "passive"))
      (node (ref "U32") (pin "1") (pinfunction "A_1") (pintype "passive"))
    )
    (net (code "115") (name "Net-(U33-A)") (class "Default")
      (node (ref "R142") (pin "1") (pinfunction "1_1") (pintype "passive"))
      (node (ref "U33") (pin "1") (pinfunction "A_1") (pintype "passive"))
    )
    (net (code "116") (name "Net-(U34-A)") (class "Default")
      (node (ref "R144") (pin "1") (pinfunction "1_1") (pintype "passive"))
      (node (ref "U34") (pin "1") (pinfunction "A_1") (pintype "passive"))
    )
    (net (code "117") (name "Net-(U35-A)") (class "Default")
      (node (ref "R147") (pin "1") (pinfunction "1_1") (pintype "passive"))
      (node (ref "U35") (pin "1") (pinfunction "A_1") (pintype "passive"))
    )
    (net (code "118") (name "Net-(U36-A)") (class "Default")
      (node (ref "R148") (pin "1") (pinfunction "1_1") (pintype "passive"))
      (node (ref "U36") (pin "1") (pinfunction "A_1") (pintype "passive"))
    )
    (net (code "119") (name "Net-(U37-A)") (class "Default")
      (node (ref "R150") (pin "1") (pinfunction "1_1") (pintype "passive"))
      (node (ref "U37") (pin "1") (pinfunction "A_1") (pintype "passive"))
    )
    (net (code "120") (name "Net-(U38-A)") (class "Default")
      (node (ref "R152") (pin "1") (pinfunction "1_1") (pintype "passive"))
      (node (ref "U38") (pin "1") (pinfunction "A_1") (pintype "passive"))
    )
    (net (code "121") (name "Net-(U39-A)") (class "Default")
      (node (ref "R154") (pin "1") (pinfunction "1_1") (pintype "passive"))
      (node (ref "U39") (pin "1") (pinfunction "A_1") (pintype "passive"))
    )
    (net (code "122") (name "Net-(U40-A)") (class "Default")
      (node (ref "R156") (pin "1") (pinfunction "1_1") (pintype "passive"))
      (node (ref "U40") (pin "1") (pinfunction "A_1") (pintype "passive"))
    )
    (net (code "123") (name "Net-(U41-A)") (class "Default")
      (node (ref "R158") (pin "1") (pinfunction "1_1") (pintype "passive"))
      (node (ref "U41") (pin "1") (pinfunction "A_1") (pintype "passive"))
    )
    (net (code "124") (name "Net-(U42-A)") (class "Default")
      (node (ref "R160") (pin "1") (pinfunction "1_1") (pintype "passive"))
      (node (ref "U42") (pin "1") (pinfunction "A_1") (pintype "passive"))
    )
    (net (code "125") (name "Net-(U46-A)") (class "Default")
      (node (ref "R107") (pin "1") (pinfunction "1_1") (pintype "passive"))
      (node (ref "U46") (pin "1") (pinfunction "A_1") (pintype "passive"))
    )
  )
)
